# 4a_-_Latching_AMS.net
KiCad netlist of a schematic drawn in Altium Designer
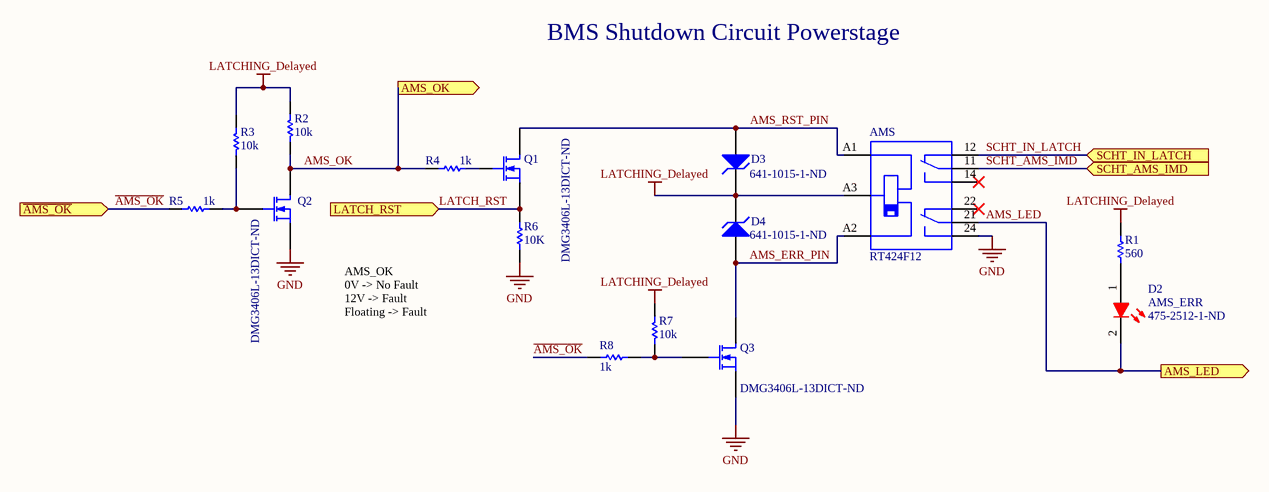
[diagram p0: 4a - Latching AMS.SchDoc]

(export (version "E")
  (design (tool "Eeschema 10.0.6"))
  (components
    (comp (ref "AMS")
      (value "RT424F12")
      (footprint "TE_5-1393243-4")
      (description "General Purpose Relay DPDT (2 Form C) 12VDC Coil Through Hole")
      (fields (field (name "MF") "TE Connectivity"))
      (libsource (lib "RT424F12") (part "RT424F12"))
    )
    (comp (ref "D2")
      (value "AMS_ERR")
      (footprint "TOSH-0603LED_RED_V")
      (description "LED, Red 0603 (1608) 63mCd")
      (fields
        (field (name "MANUFACTURER") "Toshiba")
        (field (name "PARTNUMBER") "TLSU1008A(T04)")
        (field (name "SUPPLIER PART NUMBER 1") "475-2512-1-ND")
      )
      (libsource (lib "Altium Content Vault") (part "CMP-0444-00001-1"))
    )
    (comp (ref "D3")
      (value "D Zener")
      (footprint "DO214AC")
      (description "Zener Diode")
      (fields
        (field (name "SUPPLIER PART NUMBER 1") "641-1015-1-ND")
        (field (name "PUBLISHER") "Altium Limited")
      )
      (libsource (lib "Miscellaneous Devices") (part "D Zener"))
    )
    (comp (ref "D4")
      (value "D Zener")
      (footprint "DO214AC")
      (description "Zener Diode")
      (fields
        (field (name "SUPPLIER PART NUMBER 1") "641-1015-1-ND")
        (field (name "PUBLISHER") "Altium Limited")
      )
      (libsource (lib "Miscellaneous Devices") (part "D Zener"))
    )
    (comp (ref "Q1")
      (value "~")
      (footprint "SOT-23_N")
      (description "N-Channel MOSFET")
      (fields
        (field (name "MANUFACTURER") "Infineon Technologies")
        (field (name "SUPPLIER PART NUMBER 1") "DMG3406L-13DICT-ND")
        (field (name "PUBLISHER") "Altium Limited")
      )
      (libsource (lib "Miscellaneous Devices") (part "MOSFET-N"))
    )
    (comp (ref "Q2")
      (value "~")
      (footprint "SOT-23_N")
      (description "N-Channel MOSFET")
      (fields
        (field (name "MANUFACTURER") "Infineon Technologies")
        (field (name "SUPPLIER PART NUMBER 1") "DMG3406L-13DICT-ND")
        (field (name "PUBLISHER") "Altium Limited")
      )
      (libsource (lib "Miscellaneous Devices") (part "MOSFET-N"))
    )
    (comp (ref "Q3")
      (value "~")
      (footprint "SOT-23_N")
      (description "N-Channel MOSFET")
      (fields
        (field (name "MANUFACTURER") "Infineon Technologies")
        (field (name "SUPPLIER PART NUMBER 1") "DMG3406L-13DICT-ND")
        (field (name "PUBLISHER") "Altium Limited")
      )
      (libsource (lib "Miscellaneous Devices") (part "MOSFET-N"))
    )
    (comp (ref "R1")
      (value "560")
      (footprint "RESC0603(1608)_L")
      (description "0603 (1608 Metric) Chip Resistor")
      (libsource (lib "Altium Content Vault") (part "RES_3"))
    )
    (comp (ref "R2")
      (value "RHM1.0KDCT-ND")
      (footprint "1608[0603]")
      (description "RES SMD 1.0K OHM 5% 1/4W 0603")
      (fields
        (field (name "MANUFACTURER") "Rohm Semiconductor")
        (field (name "MANUFACTURER PART NUMBER") "ESR03EZPJ102")
        (field (name "RESISTANCE (OHMS)") "10k")
      )
      (libsource (lib "Miscellaneous Devices") (part "Res1"))
    )
    (comp (ref "R3")
      (value "RHM1.0KDCT-ND")
      (footprint "1608[0603]")
      (description "RES SMD 1.0K OHM 5% 1/4W 0603")
      (fields
        (field (name "MANUFACTURER") "Rohm Semiconductor")
        (field (name "MANUFACTURER PART NUMBER") "ESR03EZPJ102")
        (field (name "RESISTANCE (OHMS)") "10k")
      )
      (libsource (lib "Miscellaneous Devices") (part "Res1"))
    )
    (comp (ref "R4")
      (value "1k")
      (footprint "1608[0603]")
      (description "RES SMD 100 OHM 5% 1/4W 0603")
      (fields
        (field (name "MANUFACTURER") "Rohm Semiconductor")
        (field (name "MANUFACTURER PART NUMBER") "ESR03EZPJ101")
        (field (name "PUBLISHER") "Altium Limited")
      )
      (libsource (lib "Miscellaneous Devices") (part "Res1"))
    )
    (comp (ref "R5")
      (value "1k")
      (footprint "1608[0603]")
      (description "RES SMD 100 OHM 5% 1/4W 0603")
      (fields
        (field (name "MANUFACTURER") "Rohm Semiconductor")
        (field (name "MANUFACTURER PART NUMBER") "ESR03EZPJ101")
        (field (name "PUBLISHER") "Altium Limited")
      )
      (libsource (lib "Miscellaneous Devices") (part "Res1"))
    )
    (comp (ref "R6")
      (value "10K")
      (footprint "1608[0603]")
      (description "RES SMD 10K OHM 5% 1/4W 0603")
      (fields
        (field (name "MANUFACTURER") "Rohm Semiconductor")
        (field (name "MANUFACTURER PART NUMBER") "ESR03EZPJ103")
        (field (name "PUBLISHER") "Altium Limited")
      )
      (libsource (lib "Miscellaneous Devices") (part "Res1"))
    )
    (comp (ref "R7")
      (value "RHM1.0KDCT-ND")
      (footprint "1608[0603]")
      (description "RES SMD 1.0K OHM 5% 1/4W 0603")
      (fields
        (field (name "MANUFACTURER") "Rohm Semiconductor")
        (field (name "MANUFACTURER PART NUMBER") "ESR03EZPJ102")
        (field (name "RESISTANCE (OHMS)") "10k")
      )
      (libsource (lib "Miscellaneous Devices") (part "Res1"))
    )
    (comp (ref "R8")
      (value "1k")
      (footprint "1608[0603]")
      (description "Resistor")
      (fields
        (field (name "MANUFACTURER") "Panasonic Electronic Components")
        (field (name "MANUFACTURER PART NUMBER") "ERJ-3EKF60R4V")
        (field (name "PUBLISHER") "Altium Limited")
      )
      (libsource (lib "Miscellaneous Devices") (part "Res1"))
    )
  )
  (nets
    (net (code "1") (name "/AMS_ERR_PIN") (class "Default")
      (node (ref "AMS") (pin "A2") (pinfunction "A2_A2") (pintype "passive"))
      (node (ref "D4") (pin "1") (pinfunction "A_1") (pintype "passive"))
      (node (ref "Q3") (pin "3") (pinfunction "D_3") (pintype "passive"))
    )
    (net (code "2") (name "/AMS_LED") (class "Default")
      (node (ref "AMS") (pin "21") (pinfunction "21_21") (pintype "passive"))
      (node (ref "D2") (pin "2") (pinfunction "K_2") (pintype "passive"))
    )
    (net (code "3") (name "/AMS_OK") (class "Default")
      (node (ref "Q2") (pin "3") (pinfunction "D_3") (pintype "passive"))
      (node (ref "R2") (pin "2") (pinfunction "2_2") (pintype "passive"))
      (node (ref "R4") (pin "1") (pinfunction "1_1") (pintype "passive"))
    )
    (net (code "4") (name "/AMS_RST_PIN") (class "Default")
      (node (ref "AMS") (pin "A1") (pinfunction "A1_A1") (pintype "passive"))
      (node (ref "D3") (pin "1") (pinfunction "A_1") (pintype "passive"))
      (node (ref "Q1") (pin "3") (pinfunction "D_3") (pintype "passive"))
    )
    (net (code "5") (name "/LATCH_RST") (class "Default")
      (node (ref "Q1") (pin "2") (pinfunction "S_2") (pintype "passive"))
      (node (ref "R6") (pin "2") (pinfunction "2_2") (pintype "passive"))
    )
    (net (code "6") (name "/SCHT_AMS_IMD") (class "Default")
      (node (ref "AMS") (pin "11") (pinfunction "11_11") (pintype "passive"))
    )
    (net (code "7") (name "/SCHT_IN_LATCH") (class "Default")
      (node (ref "AMS") (pin "12") (pinfunction "12_12") (pintype "passive"))
    )
    (net (code "8") (name "/~{AMS_OK}") (class "Default")
      (node (ref "R5") (pin "1") (pinfunction "1_1") (pintype "passive"))
      (node (ref "R8") (pin "1") (pinfunction "1_1") (pintype "passive"))
    )
    (net (code "9") (name "GND") (class "Default")
      (node (ref "AMS") (pin "24") (pinfunction "24_24") (pintype "passive"))
      (node (ref "Q2") (pin "2") (pinfunction "S_2") (pintype "passive"))
      (node (ref "Q3") (pin "2") (pinfunction "S_2") (pintype "passive"))
      (node (ref "R6") (pin "1") (pinfunction "1_1") (pintype "passive"))
    )
    (net (code "10") (name "LATCHING_Delayed") (class "Default")
      (node (ref "AMS") (pin "A3") (pinfunction "A3_A3") (pintype "passive"))
      (node (ref "D3") (pin "2") (pinfunction "K_2") (pintype "passive"))
      (node (ref "D4") (pin "2") (pinfunction "K_2") (pintype "passive"))
      (node (ref "R1") (pin "2") (pinfunction "2_2") (pintype "passive"))
      (node (ref "R2") (pin "1") (pinfunction "1_1") (pintype "passive"))
      (node (ref "R3") (pin "1") (pinfunction "1_1") (pintype "passive"))
      (node (ref "R7") (pin "1") (pinfunction "1_1") (pintype "passive"))
    )
    (net (code "11") (name "Net-(D2-A)") (class "Default")
      (node (ref "D2") (pin "1") (pinfunction "A_1") (pintype "passive"))
      (node (ref "R1") (pin "1") (pinfunction "1_1") (pintype "passive"))
    )
    (net (code "12") (name "Net-(Q1-G)") (class "Default")
      (node (ref "Q1") (pin "1") (pinfunction "G_1") (pintype "passive"))
      (node (ref "R4") (pin "2") (pinfunction "2_2") (pintype "passive"))
    )
    (net (code "13") (name "Net-(Q2-G)") (class "Default")
      (node (ref "Q2") (pin "1") (pinfunction "G_1") (pintype "passive"))
      (node (ref "R3") (pin "2") (pinfunction "2_2") (pintype "passive"))
      (node (ref "R5") (pin "2") (pinfunction "2_2") (pintype "passive"))
    )
    (net (code "14") (name "Net-(Q3-G)") (class "Default")
      (node (ref "Q3") (pin "1") (pinfunction "G_1") (pintype "passive"))
      (node (ref "R7") (pin "2") (pinfunction "2_2") (pintype "passive"))
      (node (ref "R8") (pin "2") (pinfunction "2_2") (pintype "passive"))
    )
    (net (code "15") (name "unconnected-(AMS-Pad14)") (class "Default")
      (node (ref "AMS") (pin "14") (pinfunction "14_14") (pintype "passive+no_connect"))
    )
    (net (code "16") (name "unconnected-(AMS-Pad22)") (class "Default")
      (node (ref "AMS") (pin "22") (pinfunction "22_22") (pintype "passive+no_connect"))
    )
  )
)
